# PlacaBaza.net
KiCad netlist of a schematic drawn in Altium Designer
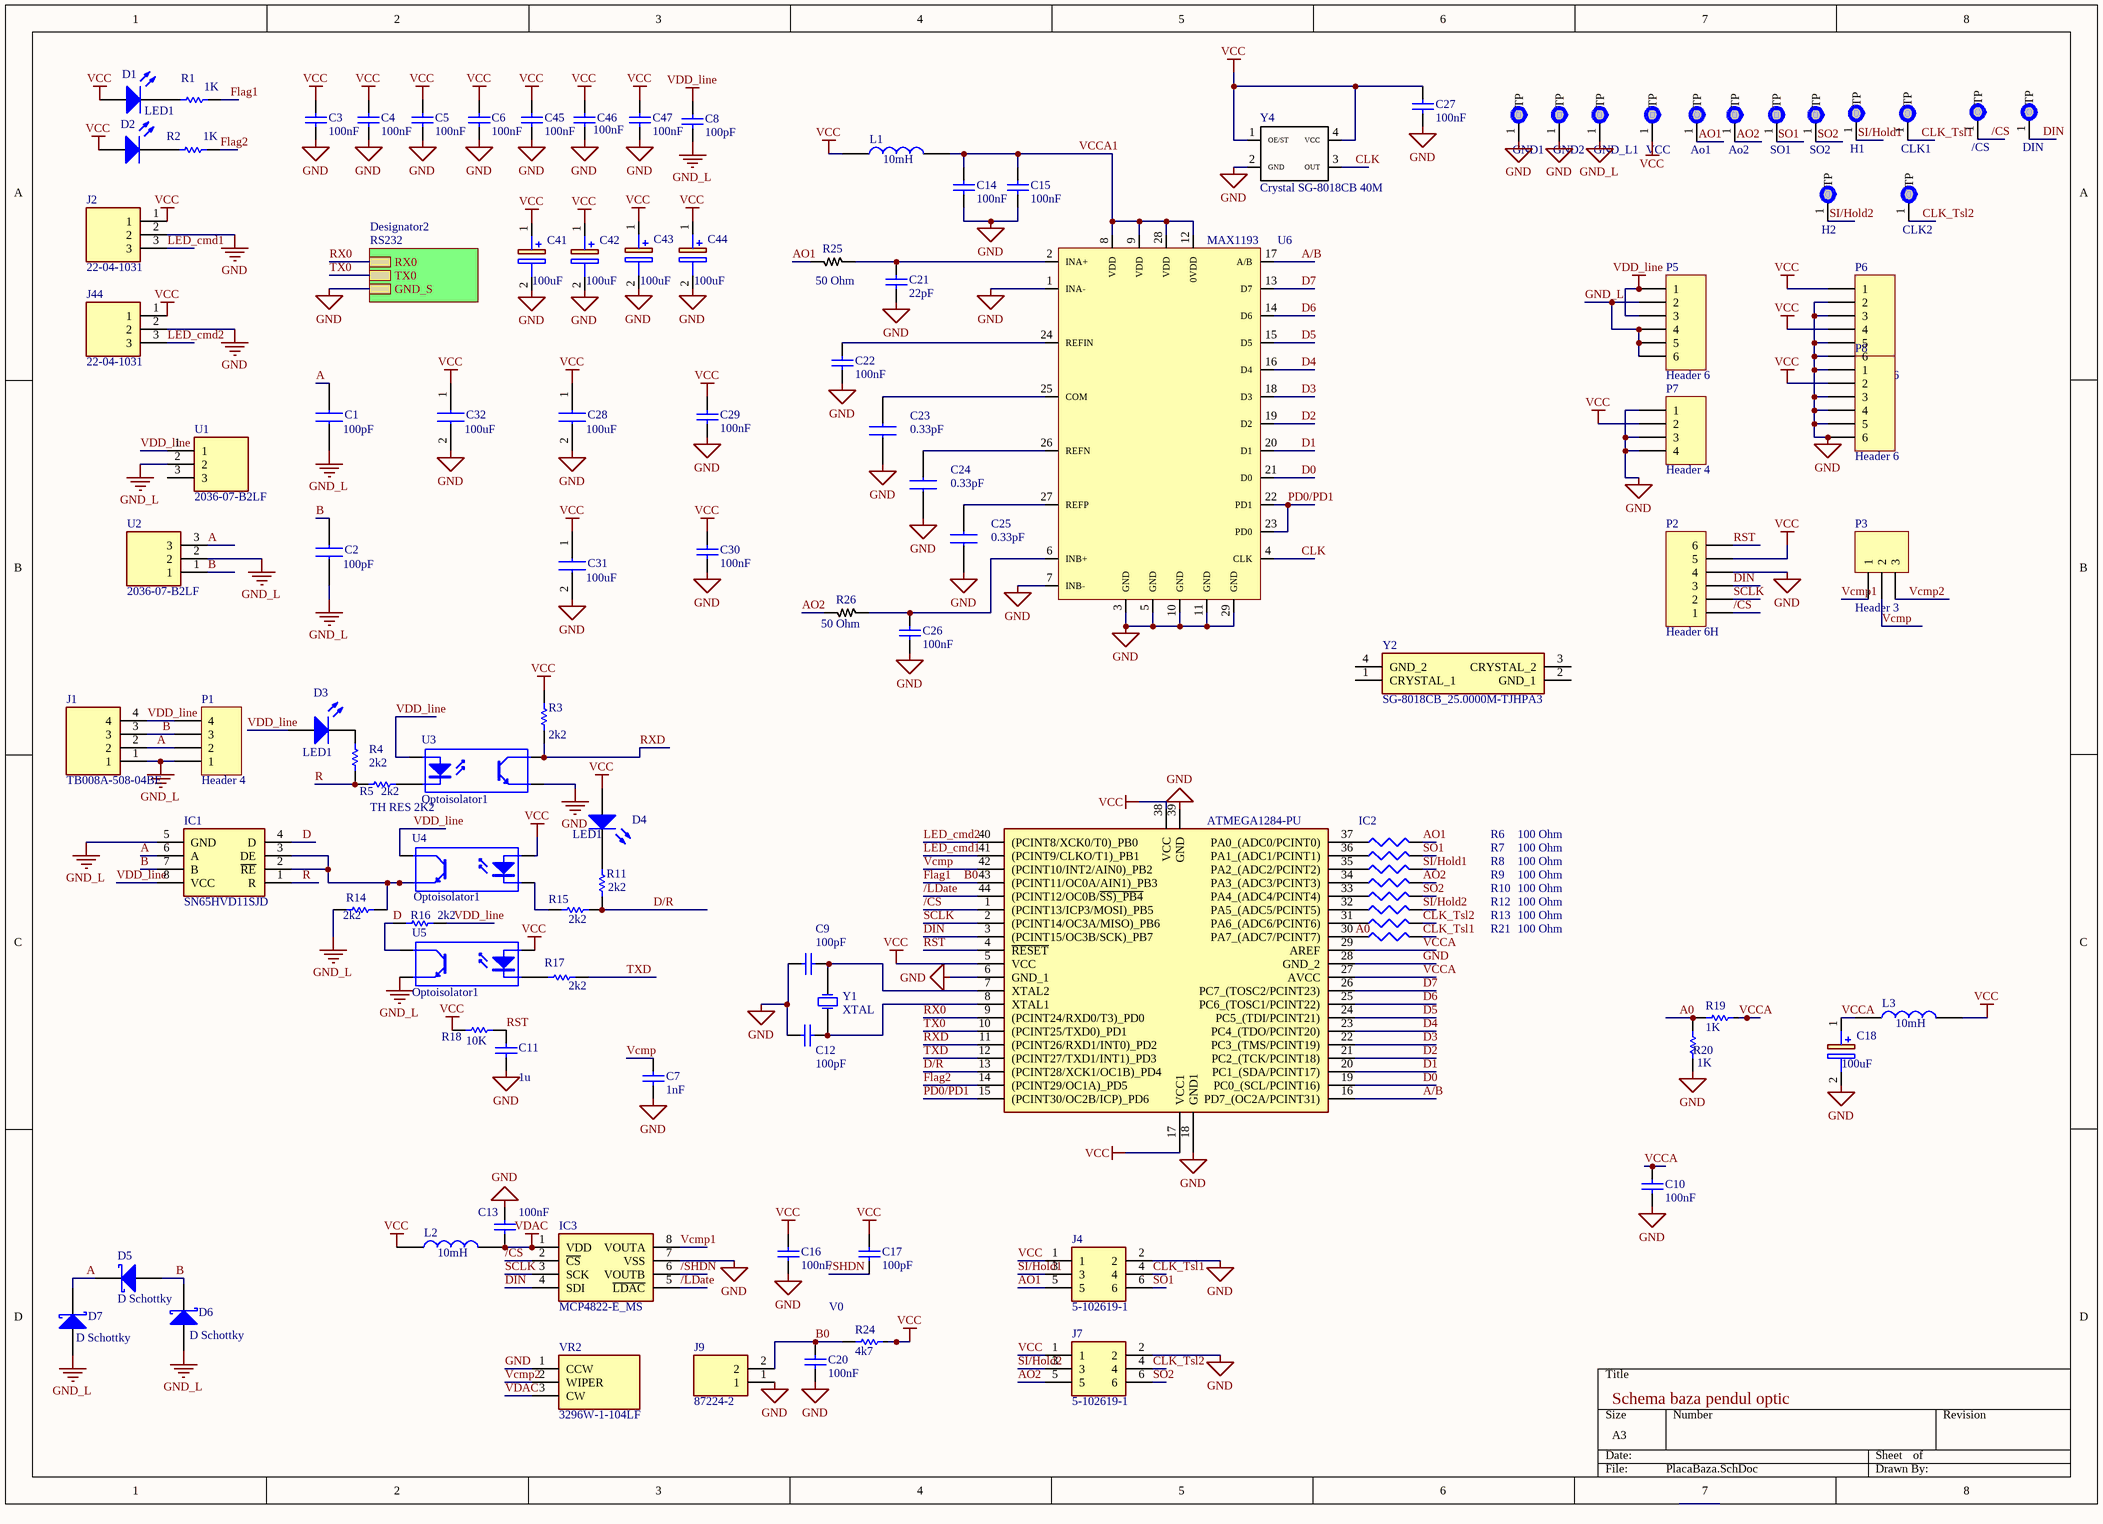
[diagram p0: PlacaBaza.SchDoc]

(export (version "E")
  (design (tool "Eeschema 10.0.6"))
  (components
    (comp (ref "/CS") (value "Testpoint") (footprint "TP") (libsource (lib "my_sch_lib") (part "Test point")))
    (comp (ref "Ao1") (value "Testpoint") (footprint "TP") (libsource (lib "my_sch_lib") (part "Test point")))
    (comp (ref "Ao2") (value "Testpoint") (footprint "TP") (libsource (lib "my_sch_lib") (part "Test point")))
    (comp (ref "C1")
      (value "100pF")
      (footprint "1206 CAP")
      (description "1206CAP 100pF")
      (fields
        (field (name "MANUFACTURER_PART_NUMBER") "04023A101FAT2A")
        (field (name "MOUSER PART NUMBER") "581-04023A101F")
      )
      (libsource (lib "*") (part "04023A101FAT2A"))
    )
    (comp (ref "C2")
      (value "100pF")
      (footprint "1206 CAP")
      (description "1206CAP 100pF")
      (fields
        (field (name "MANUFACTURER_PART_NUMBER") "04023A101FAT2A")
        (field (name "MOUSER PART NUMBER") "581-04023A101F")
      )
      (libsource (lib "*") (part "04023A101FAT2A"))
    )
    (comp (ref "C3")
      (value "100nF")
      (footprint "1206 CAP")
      (description "1206CAP 100nF")
      (fields (field (name "PUBLISHER") "Altium Limited"))
      (libsource (lib "Miscellaneous Devices") (part "Cap"))
    )
    (comp (ref "C4")
      (value "100nF")
      (footprint "1206 CAP")
      (description "1206CAP 100nF")
      (fields (field (name "PUBLISHER") "Altium Limited"))
      (libsource (lib "Miscellaneous Devices") (part "Cap"))
    )
    (comp (ref "C5")
      (value "100nF")
      (footprint "1206 CAP")
      (description "1206CAP 100nF")
      (fields (field (name "PUBLISHER") "Altium Limited"))
      (libsource (lib "Miscellaneous Devices") (part "Cap"))
    )
    (comp (ref "C6")
      (value "100nF")
      (footprint "1206 CAP")
      (description "1206CAP 100nF")
      (fields (field (name "PUBLISHER") "Altium Limited"))
      (libsource (lib "Miscellaneous Devices") (part "Cap"))
    )
    (comp (ref "C7")
      (value "1nF")
      (footprint "1206 CAP")
      (description "1206CAP 1nF")
      (fields (field (name "PUBLISHER") "Altium Limited"))
      (libsource (lib "Miscellaneous Devices") (part "Cap"))
    )
    (comp (ref "C8")
      (value "100pF")
      (footprint "1206 CAP")
      (description "1206CAP 100nF")
      (fields (field (name "PUBLISHER") "Altium Limited"))
      (libsource (lib "Miscellaneous Devices") (part "Cap"))
    )
    (comp (ref "C9")
      (value "100pF")
      (footprint "1206 CAP")
      (description "1206CAP 100pF")
      (fields (field (name "PUBLISHER") "Altium Limited"))
      (libsource (lib "Miscellaneous Devices") (part "Cap Semi"))
    )
    (comp (ref "C10")
      (value "100nF")
      (footprint "1206 CAP")
      (description "1206CAP 100nF")
      (fields (field (name "PUBLISHER") "Altium Limited"))
      (libsource (lib "Miscellaneous Devices") (part "Cap"))
    )
    (comp (ref "C11")
      (value "1u")
      (footprint "1206 CAP")
      (description "1206CAP 1uF")
      (fields (field (name "PUBLISHER") "Altium Limited"))
      (libsource (lib "Miscellaneous Devices") (part "Cap"))
    )
    (comp (ref "C12")
      (value "100pF")
      (footprint "1206 CAP")
      (description "1206CAP 100pF")
      (fields (field (name "PUBLISHER") "Altium Limited"))
      (libsource (lib "Miscellaneous Devices") (part "Cap Semi"))
    )
    (comp (ref "C13")
      (value "100nF")
      (footprint "1206 CAP")
      (description "1206CAP 100nF")
      (fields (field (name "PUBLISHER") "Altium Limited"))
      (libsource (lib "Miscellaneous Devices") (part "Cap"))
    )
    (comp (ref "C14")
      (value "100nF")
      (footprint "1206 CAP")
      (description "1206CAP 100nF")
      (fields (field (name "PUBLISHER") "Altium Limited"))
      (libsource (lib "Miscellaneous Devices") (part "Cap"))
    )
    (comp (ref "C15")
      (value "100nF")
      (footprint "1206 CAP")
      (description "1206CAP 100nF")
      (fields (field (name "PUBLISHER") "Altium Limited"))
      (libsource (lib "Miscellaneous Devices") (part "Cap"))
    )
    (comp (ref "C16")
      (value "100nF")
      (footprint "1206 CAP")
      (description "1206CAP 100nF")
      (fields (field (name "PUBLISHER") "Altium Limited"))
      (libsource (lib "Miscellaneous Devices") (part "Cap"))
    )
    (comp (ref "C17")
      (value "100pF")
      (footprint "1206 CAP")
      (description "1206CAP 100pF")
      (fields (field (name "PUBLISHER") "Altium Limited"))
      (libsource (lib "Miscellaneous Devices") (part "Cap"))
    )
    (comp (ref "C18")
      (value "100uF")
      (footprint "CAPPRD275W50D630H1100")
      (description "polarized cap 2.75 pitch")
      (fields
        (field (name "MANUFACTURER_PART_NUMBER") "MAL215299601E3")
        (field (name "MOUSER PART NUMBER") "594-MAL215299601E3")
      )
      (libsource (lib "*") (part "MAL215299601E3"))
    )
    (comp (ref "C20")
      (value "100nF")
      (footprint "1206 CAP")
      (description "1206CAP 100nF")
      (fields (field (name "PUBLISHER") "Altium Limited"))
      (libsource (lib "Miscellaneous Devices") (part "Cap"))
    )
    (comp (ref "C21")
      (value "22pF")
      (footprint "1206 CAP")
      (description "1206CAP 22pF")
      (fields (field (name "PUBLISHER") "Altium Limited"))
      (libsource (lib "Miscellaneous Devices") (part "Cap"))
    )
    (comp (ref "C22")
      (value "100nF")
      (footprint "1206 CAP")
      (description "1206CAP 100nF")
      (fields (field (name "PUBLISHER") "Altium Limited"))
      (libsource (lib "Miscellaneous Devices") (part "Cap"))
    )
    (comp (ref "C23")
      (value "0.33pF")
      (footprint "0805")
      (description "1206CAP 0.33uF")
      (fields
        (field (name "MANUFACTURER_PART_NUMBER") "08055A150JAT2A")
        (field (name "MOUSER PART NUMBER") "581-08055A150J")
      )
      (libsource (lib "*") (part "08055A150JAT2A"))
    )
    (comp (ref "C24")
      (value "0.33pF")
      (footprint "0805")
      (description "1206CAP 0.33uF")
      (fields
        (field (name "MANUFACTURER_PART_NUMBER") "08055A150JAT2A")
        (field (name "MOUSER PART NUMBER") "581-08055A150J")
      )
      (libsource (lib "*") (part "08055A150JAT2A"))
    )
    (comp (ref "C25")
      (value "0.33pF")
      (footprint "0805")
      (description "1206CAP 0.33uF")
      (fields
        (field (name "MANUFACTURER_PART_NUMBER") "08055A150JAT2A")
        (field (name "MOUSER PART NUMBER") "581-08055A150J")
      )
      (libsource (lib "*") (part "08055A150JAT2A"))
    )
    (comp (ref "C26")
      (value "100nF")
      (footprint "1206 CAP")
      (description "1206CAP 100nF")
      (fields (field (name "PUBLISHER") "Altium Limited"))
      (libsource (lib "Miscellaneous Devices") (part "Cap"))
    )
    (comp (ref "C27")
      (value "100nF")
      (footprint "1206 CAP")
      (description "1206CAP 100nF")
      (fields (field (name "PUBLISHER") "Altium Limited"))
      (libsource (lib "Miscellaneous Devices") (part "Cap"))
    )
    (comp (ref "C28")
      (value "100uF")
      (footprint "SamacSys:CAPPRD275W50D630H1100")
      (description "polarized cap 2.75mm pitch")
      (fields
        (field (name "MANUFACTURER_PART_NUMBER") "MAL203855101E3")
        (field (name "MOUSER PART NUMBER") "594-MAL203855101E3")
      )
      (libsource (lib "SamacSys") (part "MAL203855101E3"))
    )
    (comp (ref "C29")
      (value "100nF")
      (footprint "1206 CAP")
      (description "1206CAP 100nF")
      (fields (field (name "PUBLISHER") "Altium Limited"))
      (libsource (lib "Miscellaneous Devices") (part "Cap"))
    )
    (comp (ref "C30")
      (value "100nF")
      (footprint "1206 CAP")
      (description "1206CAP 100nF")
      (fields (field (name "PUBLISHER") "Altium Limited"))
      (libsource (lib "Miscellaneous Devices") (part "Cap"))
    )
    (comp (ref "C31")
      (value "100uF")
      (footprint "SamacSys:CAPPRD275W50D630H1100")
      (description "polarized cap 2.75mm pitch")
      (fields
        (field (name "MANUFACTURER_PART_NUMBER") "MAL203855101E3")
        (field (name "MOUSER PART NUMBER") "594-MAL203855101E3")
      )
      (libsource (lib "SamacSys") (part "MAL203855101E3"))
    )
    (comp (ref "C32")
      (value "100uF")
      (footprint "SamacSys:CAPPRD275W50D630H1100")
      (description "polarized cap 2.75mm pitch")
      (fields
        (field (name "MANUFACTURER_PART_NUMBER") "MAL203855101E3")
        (field (name "MOUSER PART NUMBER") "594-MAL203855101E3")
      )
      (libsource (lib "SamacSys") (part "MAL203855101E3"))
    )
    (comp (ref "C41")
      (value "100uF")
      (footprint "CAPPRD275W50D630H1100")
      (description "polarized cap 2.75mm pitch")
      (fields
        (field (name "MANUFACTURER_PART_NUMBER") "MAL215299601E3")
        (field (name "MOUSER PART NUMBER") "594-MAL215299601E3")
      )
      (libsource (lib "*") (part "MAL215299601E3"))
    )
    (comp (ref "C42")
      (value "100uF")
      (footprint "CAPPRD275W50D630H1100")
      (description "polarized cap 2.75mm pitch")
      (fields
        (field (name "MANUFACTURER_PART_NUMBER") "MAL215299601E3")
        (field (name "MOUSER PART NUMBER") "594-MAL215299601E3")
      )
      (libsource (lib "*") (part "MAL215299601E3"))
    )
    (comp (ref "C43")
      (value "100uF")
      (footprint "CAPPRD275W50D630H1100")
      (description "polarized cap 2.75mm pitch")
      (fields
        (field (name "MANUFACTURER_PART_NUMBER") "MAL215299601E3")
        (field (name "MOUSER PART NUMBER") "594-MAL215299601E3")
      )
      (libsource (lib "*") (part "MAL215299601E3"))
    )
    (comp (ref "C44")
      (value "100uF")
      (footprint "CAPPRD275W50D630H1100")
      (description "polarized cap 2.75mm pitch")
      (fields
        (field (name "MANUFACTURER_PART_NUMBER") "MAL215299601E3")
        (field (name "MOUSER PART NUMBER") "594-MAL215299601E3")
      )
      (libsource (lib "*") (part "MAL215299601E3"))
    )
    (comp (ref "C45")
      (value "100nF")
      (footprint "1206 CAP")
      (description "1206CAP 100nF")
      (fields (field (name "PUBLISHER") "Altium Limited"))
      (libsource (lib "Miscellaneous Devices") (part "Cap"))
    )
    (comp (ref "C46")
      (value "100nF")
      (footprint "1206 CAP")
      (description "1206CAP 100nF")
      (fields (field (name "PUBLISHER") "Altium Limited"))
      (libsource (lib "Miscellaneous Devices") (part "Cap"))
    )
    (comp (ref "C47")
      (value "100nF")
      (footprint "1206 CAP")
      (description "1206CAP 100nF")
      (fields (field (name "PUBLISHER") "Altium Limited"))
      (libsource (lib "Miscellaneous Devices") (part "Cap"))
    )
    (comp (ref "CLK1")
      (value "Testpoint")
      (footprint "TP")
      (libsource (lib "my_sch_lib") (part "Test point"))
    )
    (comp (ref "CLK2")
      (value "Testpoint")
      (footprint "TP")
      (libsource (lib "my_sch_lib") (part "Test point"))
    )
    (comp (ref "D1")
      (value "LED1")
      (footprint "LED-1")
      (description "Typical RED GaAs LED")
      (fields (field (name "PUBLISHER") "Altium Limited"))
      (libsource (lib "Miscellaneous Devices") (part "LED1"))
    )
    (comp (ref "D2")
      (value "LED1")
      (footprint "LED-1")
      (description "Typical RED GaAs LED")
      (fields (field (name "PUBLISHER") "Altium Limited"))
      (libsource (lib "Miscellaneous Devices") (part "LED1"))
    )
    (comp (ref "D3")
      (value "LED1")
      (footprint "Miscellaneous Devices:C1206")
      (description "Typical RED GaAs LED")
      (fields (field (name "PUBLISHER") "Altium Limited"))
      (libsource (lib "Miscellaneous Devices") (part "LED1"))
    )
    (comp (ref "D4")
      (value "LED1")
      (footprint "Miscellaneous Devices:C1206")
      (description "Typical RED GaAs LED")
      (fields (field (name "PUBLISHER") "Altium Limited"))
      (libsource (lib "Miscellaneous Devices") (part "LED1"))
    )
    (comp (ref "D5")
      (value "D Schottky")
      (footprint "SMB")
      (description "Schottky Diode")
      (fields (field (name "PUBLISHER") "Altium Limited"))
      (libsource (lib "Miscellaneous Devices") (part "D Schottky"))
    )
    (comp (ref "D6")
      (value "D Schottky")
      (footprint "SMB")
      (description "Schottky Diode")
      (fields (field (name "PUBLISHER") "Altium Limited"))
      (libsource (lib "Miscellaneous Devices") (part "D Schottky"))
    )
    (comp (ref "D7")
      (value "D Schottky")
      (footprint "SMB")
      (description "Schottky Diode")
      (fields (field (name "PUBLISHER") "Altium Limited"))
      (libsource (lib "Miscellaneous Devices") (part "D Schottky"))
    )
    (comp (ref "DIN") (value "Testpoint") (footprint "TP") (libsource (lib "my_sch_lib") (part "Test point")))
    (comp (ref "GND1")
      (value "Testpoint")
      (footprint "TP")
      (libsource (lib "my_sch_lib") (part "Test point"))
    )
    (comp (ref "GND2")
      (value "Testpoint")
      (footprint "TP")
      (libsource (lib "my_sch_lib") (part "Test point"))
    )
    (comp (ref "GND_L1")
      (value "Testpoint")
      (footprint "TP")
      (libsource (lib "my_sch_lib") (part "Test point"))
    )
    (comp (ref "H1") (value "Testpoint") (footprint "TP") (libsource (lib "my_sch_lib") (part "Test point")))
    (comp (ref "H2") (value "Testpoint") (footprint "TP") (libsource (lib "my_sch_lib") (part "Test point")))
    (comp (ref "IC1")
      (value "SN65HVD11SJD")
      (footprint "Miscellaneous Devices:DIP-8")
      (description "Integrated Circuit")
      (fields (field (name "MOUSER PART NUMBER") "595-SN65HVD11SJD"))
      (libsource (lib "*") (part "SN65HVD11SJD"))
    )
    (comp (ref "IC2")
      (value "ATMEGA1284-PU")
      (footprint "SamacSys:QFP80P1200X1200X120-44N")
      (description "Integrated Circuit")
      (fields (field (name "MOUSER PART NUMBER") "556-ATMEGA1284-PU"))
      (libsource (lib "my_sch_lib") (part "ATMEGA1284-PU"))
    )
    (comp (ref "IC3")
      (value "MCP4822-E_MS")
      (footprint "SamacSys:SOP65P490X110-8N")
      (description "Integrated Circuit")
      (fields
        (field (name "MANUFACTURER_PART_NUMBER") "MCP4822-E/MS")
        (field (name "MOUSER PART NUMBER") "579-MCP4822-E/MS")
      )
      (libsource (lib "*") (part "MCP4822-E_MS"))
    )
    (comp (ref "J1")
      (value "TB008A-508-04BE")
      (footprint "Miscellaneous Connectors:HDR1X4")
      (description "Connector")
      (fields (field (name "MOUSER PART NUMBER") "490-TB008A-508-04BE"))
      (libsource (lib "*") (part "TB008A-508-04BE"))
    )
    (comp (ref "J2")
      (value "22-04-1031")
      (footprint "SamacSys:SHDR3W64P0X250_1X3_700X580X1170P")
      (description "Connector")
      (fields (field (name "MOUSER PART NUMBER") "538-22-04-1031"))
      (libsource (lib "*") (part "22-04-1031"))
    )
    (comp (ref "J4")
      (value "5-102619-1")
      (footprint "SamacSys:SHDR6W66P254_2X3_1473X1016X1118P")
      (description "Connector")
      (fields (field (name "MOUSER PART NUMBER") "571-5-102619-1"))
      (libsource (lib "*") (part "5-102619-1"))
    )
    (comp (ref "J7")
      (value "5-102619-1")
      (footprint "SamacSys:SHDR6W66P254_2X3_1473X1016X1118P")
      (description "Connector")
      (fields (field (name "MOUSER PART NUMBER") "571-5-102619-1"))
      (libsource (lib "*") (part "5-102619-1"))
    )
    (comp (ref "J9")
      (value "87224-2")
      (footprint "SamacSys:872242")
      (description "Connector")
      (fields (field (name "MOUSER PART NUMBER") "571-872242"))
      (libsource (lib "*") (part "87224-2"))
    )
    (comp (ref "J44")
      (value "22-04-1031")
      (footprint "SamacSys:SHDR3W64P0X250_1X3_700X580X1170P")
      (description "Connector")
      (fields (field (name "MOUSER PART NUMBER") "538-22-04-1031"))
      (libsource (lib "*") (part "22-04-1031"))
    )
    (comp (ref "L1")
      (value "10mH")
      (footprint "SamacSys:RLB0608471KL")
      (description "Inductor")
      (fields
        (field (name "MANUFACTURER_PART_NUMBER") "RLB0608-471KL")
        (field (name "MOUSER PART NUMBER") "652-RLB0608-471KL")
      )
      (libsource (lib "SamacSys") (part "RLB0608-471KL"))
    )
    (comp (ref "L2")
      (value "10mH")
      (footprint "SamacSys:RLB0608471KL")
      (description "Inductor")
      (fields
        (field (name "MANUFACTURER_PART_NUMBER") "RLB0608-471KL")
        (field (name "MOUSER PART NUMBER") "652-RLB0608-471KL")
      )
      (libsource (lib "SamacSys") (part "RLB0608-471KL"))
    )
    (comp (ref "L3")
      (value "10mH")
      (footprint "SamacSys:RLB0608471KL")
      (description "Inductor")
      (fields
        (field (name "MANUFACTURER_PART_NUMBER") "RLB0608-471KL")
        (field (name "MOUSER PART NUMBER") "652-RLB0608-471KL")
      )
      (libsource (lib "SamacSys") (part "RLB0608-471KL"))
    )
    (comp (ref "P1")
      (value "Header 4")
      (footprint "HDR1X4")
      (description "Header, 4-Pin")
      (fields (field (name "PUBLISHER") "Altium Limited"))
      (libsource (lib "") (part "Header 4_1"))
    )
    (comp (ref "P2")
      (value "Header 6H")
      (footprint "Miscellaneous Connectors:HDR1X6")
      (description "Header, 6-Pin, Right Angle")
      (fields (field (name "PUBLISHER") "Altium Limited"))
      (libsource (lib "Miscellaneous Connectors") (part "Header 6H"))
    )
    (comp (ref "P3")
      (value "Header 3")
      (footprint "HDR1X3")
      (description "Header, 3-Pin")
      (fields (field (name "PUBLISHER") "Altium Limited"))
      (libsource (lib "Miscellaneous Connectors") (part "Header 3"))
    )
    (comp (ref "P5")
      (value "Header 6")
      (footprint "HDR1X6")
      (description "Header, 6-Pin")
      (fields (field (name "PUBLISHER") "Altium Limited"))
      (libsource (lib "Miscellaneous Connectors") (part "Header 6"))
    )
    (comp (ref "P6")
      (value "Header 6")
      (footprint "HDR1X6")
      (description "Header, 6-Pin")
      (fields (field (name "PUBLISHER") "Altium Limited"))
      (libsource (lib "Miscellaneous Connectors") (part "Header 6"))
    )
    (comp (ref "P7")
      (value "Header 4")
      (footprint "HDR1X4")
      (description "Header, 4-Pin")
      (fields (field (name "PUBLISHER") "Altium Limited"))
      (libsource (lib "Miscellaneous Connectors") (part "Header 4"))
    )
    (comp (ref "P8")
      (value "Header 6")
      (footprint "HDR1X6")
      (description "Header, 6-Pin")
      (fields (field (name "PUBLISHER") "Altium Limited"))
      (libsource (lib "Miscellaneous Connectors") (part "Header 6"))
    )
    (comp (ref "R1")
      (value "1K")
      (footprint "AXIAL-0.3")
      (description "TH RES 1K")
      (fields (field (name "PUBLISHER") "Altium Limited"))
      (libsource (lib "Miscellaneous Devices") (part "Res1"))
    )
    (comp (ref "R2")
      (value "1K")
      (footprint "AXIAL-0.3")
      (description "TH RES 1K")
      (fields (field (name "PUBLISHER") "Altium Limited"))
      (libsource (lib "Miscellaneous Devices") (part "Res1"))
    )
    (comp (ref "R3")
      (value "2k2")
      (footprint "AXIAL-0.3")
      (description "TH RES 2K2")
      (fields (field (name "PUBLISHER") "Altium Limited"))
      (libsource (lib "Miscellaneous Devices") (part "Res1"))
    )
    (comp (ref "R4")
      (value "2k2")
      (footprint "AXIAL-0.3")
      (description "TH RES 2K2")
      (fields (field (name "PUBLISHER") "Altium Limited"))
      (libsource (lib "Miscellaneous Devices") (part "Res1"))
    )
    (comp (ref "R5")
      (value "TH RES 2K2")
      (footprint "AXIAL-0.3")
      (fields (field (name "ALTIUM_VALUE") "2k2") (field (name "PUBLISHER") "Altium Limited"))
      (libsource (lib "Miscellaneous Devices") (part "Res1"))
    )
    (comp (ref "R6")
      (value "100 Ohm")
      (footprint "0805")
      (description "0805RES 100 OHM")
      (fields (field (name "PUBLISHER") "Altium Limited"))
      (libsource (lib "Miscellaneous Devices") (part "Res3"))
    )
    (comp (ref "R7")
      (value "100 Ohm")
      (footprint "0805")
      (description "0805RES 100 OHM")
      (fields (field (name "PUBLISHER") "Altium Limited"))
      (libsource (lib "Miscellaneous Devices") (part "Res3"))
    )
    (comp (ref "R8")
      (value "100 Ohm")
      (footprint "0805")
      (description "0805RES 100 OHM")
      (fields (field (name "PUBLISHER") "Altium Limited"))
      (libsource (lib "Miscellaneous Devices") (part "Res3"))
    )
    (comp (ref "R9")
      (value "100 Ohm")
      (footprint "0805")
      (description "0805RES 100 OHM")
      (fields (field (name "PUBLISHER") "Altium Limited"))
      (libsource (lib "Miscellaneous Devices") (part "Res3"))
    )
    (comp (ref "R10")
      (value "100 Ohm")
      (footprint "0805")
      (description "0805RES 100 OHM")
      (fields (field (name "PUBLISHER") "Altium Limited"))
      (libsource (lib "Miscellaneous Devices") (part "Res3"))
    )
    (comp (ref "R11")
      (value "2k2")
      (footprint "AXIAL-0.3")
      (description "TH RES 2K2")
      (fields (field (name "PUBLISHER") "Altium Limited"))
      (libsource (lib "Miscellaneous Devices") (part "Res1"))
    )
    (comp (ref "R12")
      (value "100 Ohm")
      (footprint "0805")
      (description "0805RES 100 OHM")
      (fields (field (name "PUBLISHER") "Altium Limited"))
      (libsource (lib "Miscellaneous Devices") (part "Res3"))
    )
    (comp (ref "R13")
      (value "100 Ohm")
      (footprint "0805")
      (description "0805RES 100 OHM")
      (fields (field (name "PUBLISHER") "Altium Limited"))
      (libsource (lib "Miscellaneous Devices") (part "Res3"))
    )
    (comp (ref "R14")
      (value "2k2")
      (footprint "AXIAL-0.3")
      (description "TH RES 2K2")
      (fields (field (name "PUBLISHER") "Altium Limited"))
      (libsource (lib "Miscellaneous Devices") (part "Res1"))
    )
    (comp (ref "R15")
      (value "2k2")
      (footprint "AXIAL-0.3")
      (description "TH RES 2K2")
      (fields (field (name "PUBLISHER") "Altium Limited"))
      (libsource (lib "Miscellaneous Devices") (part "Res1"))
    )
    (comp (ref "R16")
      (value "2k2")
      (footprint "AXIAL-0.3")
      (description "TH RES 2K2")
      (fields (field (name "PUBLISHER") "Altium Limited"))
      (libsource (lib "Miscellaneous Devices") (part "Res1"))
    )
    (comp (ref "R17")
      (value "2k2")
      (footprint "AXIAL-0.3")
      (description "TH RES 2K2")
      (fields (field (name "PUBLISHER") "Altium Limited"))
      (libsource (lib "Miscellaneous Devices") (part "Res1"))
    )
    (comp (ref "R18")
      (value "10K")
      (footprint "Miscellaneous Devices:C1206")
      (description "TH RES 2K2")
      (fields (field (name "PUBLISHER") "Altium Limited"))
      (libsource (lib "Miscellaneous Devices") (part "Res1"))
    )
    (comp (ref "R19")
      (value "1K")
      (footprint "1206 CAP")
      (description "1206RES 1K")
      (fields (field (name "PUBLISHER") "Altium Limited"))
      (libsource (lib "Miscellaneous Devices") (part "Res1"))
    )
    (comp (ref "R20")
      (value "1K")
      (footprint "1206 CAP")
      (description "1206RES 1K")
      (fields (field (name "PUBLISHER") "Altium Limited"))
      (libsource (lib "Miscellaneous Devices") (part "Res1"))
    )
    (comp (ref "R21")
      (value "100 Ohm")
      (footprint "0805")
      (description "0805RES 100 OHM")
      (fields (field (name "PUBLISHER") "Altium Limited"))
      (libsource (lib "Miscellaneous Devices") (part "Res3"))
    )
    (comp (ref "R24")
      (value "4k7")
      (footprint "1206 CAP")
      (description "1206RES 4K7")
      (fields (field (name "PUBLISHER") "Altium Limited"))
      (libsource (lib "Miscellaneous Devices") (part "Res1"))
    )
    (comp (ref "R25")
      (value "50 Ohm")
      (footprint "0805")
      (description "0805RES 50 OHM")
      (libsource (lib "Basic components") (part "RES 0402"))
    )
    (comp (ref "R26")
      (value "50 Ohm")
      (footprint "0805")
      (description "0805RES 50 OHM")
      (libsource (lib "Basic components") (part "RES 0402"))
    )
    (comp (ref "SO1") (value "Testpoint") (footprint "TP") (libsource (lib "my_sch_lib") (part "Test point")))
    (comp (ref "SO2") (value "Testpoint") (footprint "TP") (libsource (lib "my_sch_lib") (part "Test point")))
    (comp (ref "U1")
      (value "2036-07-B2LF")
      (footprint "SamacSys:203607B2LF")
      (description "Undefined or Miscellaneous")
      (fields (field (name "MOUSER PART NUMBER") "652-2036-07-B2LF"))
      (libsource (lib "*") (part "2036-07-B2LF"))
    )
    (comp (ref "U2")
      (value "2036-07-B2LF")
      (footprint "SamacSys:203607B2LF")
      (description "Undefined or Miscellaneous")
      (fields (field (name "MOUSER PART NUMBER") "652-2036-07-B2LF"))
      (libsource (lib "") (part "2036-07-B2LF_1"))
    )
    (comp (ref "U3")
      (value "Optoisolator1")
      (footprint "DIP-4")
      (description "4-Pin Phototransistor Optocoupler")
      (fields (field (name "PUBLISHER") "Altium Limited"))
      (libsource (lib "Miscellaneous Devices") (part "Optoisolator1"))
    )
    (comp (ref "U4")
      (value "Optoisolator1")
      (footprint "DIP-4")
      (description "4-Pin Phototransistor Optocoupler")
      (fields (field (name "PUBLISHER") "Altium Limited"))
      (libsource (lib "Miscellaneous Devices") (part "Optoisolator1"))
    )
    (comp (ref "U5")
      (value "Optoisolator1")
      (footprint "DIP-4")
      (description "4-Pin Phototransistor Optocoupler")
      (fields (field (name "PUBLISHER") "Altium Limited"))
      (libsource (lib "Miscellaneous Devices") (part "Optoisolator1"))
    )
    (comp (ref "U6")
      (value "MAX1193")
      (footprint "QFN50P500X500X80_HS-29N")
      (libsource (lib "my_sch_lib") (part "MAX1193"))
    )
    (comp (ref "VCC") (value "Testpoint") (footprint "TP") (libsource (lib "my_sch_lib") (part "Test point")))
    (comp (ref "VR2")
      (value "3296W-1-104LF")
      (footprint "SamacSys:3296W-1")
      (description "Variable Resistor")
      (fields (field (name "MOUSER PART NUMBER") "652-3296W-1-104LF"))
      (libsource (lib "*") (part "3296W-1-104LF"))
    )
    (comp (ref "Y1")
      (value "XTAL")
      (footprint "Miscellaneous Devices:RAD-0.2")
      (description "Crystal Oscillator")
      (fields (field (name "PUBLISHER") "Altium Limited"))
      (libsource (lib "Miscellaneous Devices") (part "XTAL"))
    )
    (comp (ref "Y2")
      (value "SG-8018CB_25.0000M-TJHPA3")
      (footprint "SamacSys:SG8018CB250000MTJHPA3")
      (description "Crystal or Oscillator")
      (fields
        (field (name "MANUFACTURER_PART_NUMBER") "SG-8018CB 25.0000M-TJHPA3")
        (field (name "MOUSER PART NUMBER") "732-CB25M-TJHPA3")
      )
      (libsource (lib "SamacSys") (part "SG-8018CB_25.0000M-TJHPA3"))
    )
    (comp (ref "Y4")
      (value "Crystal SG-8018CB 40M")
      (footprint "SG-8018CB")
      (libsource (lib "my_sch_lib") (part "Crystal SG-8018CB 40M"))
    )
  )
  (nets
    (net (code "1") (name "/A") (class "Default")
      (node (ref "C1") (pin "2") (pinfunction "2_2") (pintype "passive"))
      (node (ref "D5") (pin "2") (pinfunction "K_2") (pintype "passive"))
      (node (ref "D7") (pin "2") (pinfunction "K_2") (pintype "passive"))
      (node (ref "IC1") (pin "6") (pinfunction "A_6") (pintype "passive"))
      (node (ref "J1") (pin "2") (pinfunction "2_2") (pintype "passive"))
      (node (ref "P1") (pin "2") (pinfunction "2_2") (pintype "passive"))
      (node (ref "U2") (pin "3") (pinfunction "3_3") (pintype "passive"))
    )
    (net (code "2") (name "/A0") (class "Default")
      (node (ref "IC2") (pin "30") (pinfunction "PA7_(ADC7/PCINT7)_30") (pintype "passive"))
      (node (ref "R19") (pin "1") (pinfunction "1_1") (pintype "passive"))
      (node (ref "R20") (pin "2") (pinfunction "2_2") (pintype "passive"))
      (node (ref "R21") (pin "1") (pinfunction "1_1") (pintype "passive"))
    )
    (net (code "3") (name "/AO1") (class "Default")
      (node (ref "Ao1") (pin "1") (pinfunction "TP_1") (pintype "passive"))
      (node (ref "J4") (pin "5") (pinfunction "5_5") (pintype "passive"))
      (node (ref "R25") (pin "2") (pinfunction "2_2") (pintype "passive"))
      (node (ref "R6") (pin "2") (pinfunction "2_2") (pintype "passive"))
    )
    (net (code "4") (name "/AO2") (class "Default")
      (node (ref "Ao2") (pin "1") (pinfunction "TP_1") (pintype "passive"))
      (node (ref "J7") (pin "5") (pinfunction "5_5") (pintype "passive"))
      (node (ref "R26") (pin "2") (pinfunction "2_2") (pintype "passive"))
      (node (ref "R9") (pin "2") (pinfunction "2_2") (pintype "passive"))
    )
    (net (code "5") (name "/A{slash}B") (class "Default")
      (node (ref "IC2") (pin "16") (pinfunction "PD7_(OC2A/PCINT31)_16") (pintype "passive"))
      (node (ref "U6") (pin "17") (pinfunction "A/B_17") (pintype "passive"))
    )
    (net (code "6") (name "/B") (class "Default")
      (node (ref "C2") (pin "2") (pinfunction "2_2") (pintype "passive"))
      (node (ref "D5") (pin "1") (pinfunction "A_1") (pintype "passive"))
      (node (ref "D6") (pin "2") (pinfunction "K_2") (pintype "passive"))
      (node (ref "IC1") (pin "7") (pinfunction "B_7") (pintype "passive"))
      (node (ref "J1") (pin "3") (pinfunction "3_3") (pintype "passive"))
      (node (ref "P1") (pin "3") (pinfunction "3_3") (pintype "passive"))
      (node (ref "U2") (pin "1") (pinfunction "1_1") (pintype "passive"))
    )
    (net (code "7") (name "/B0") (class "Default")
      (node (ref "C20") (pin "2") (pinfunction "2_2") (pintype "passive"))
      (node (ref "IC2") (pin "43") (pinfunction "(PCINT11/OC0A/AIN1)_PB3_43") (pintype "passive"))
      (node (ref "J9") (pin "2") (pinfunction "2_2") (pintype "passive"))
      (node (ref "R1") (pin "1") (pinfunction "1_1") (pintype "passive"))
      (node (ref "R24") (pin "1") (pinfunction "1_1") (pintype "passive"))
    )
    (net (code "8") (name "/CLK") (class "Default")
      (node (ref "U6") (pin "4") (pinfunction "CLK_4") (pintype "passive"))
      (node (ref "Y4") (pin "3") (pinfunction "OUT_3") (pintype "passive"))
    )
    (net (code "9") (name "/CLK_Tsl1") (class "Default")
      (node (ref "CLK1") (pin "1") (pinfunction "TP_1") (pintype "passive"))
      (node (ref "J4") (pin "4") (pinfunction "4_4") (pintype "passive"))
      (node (ref "R21") (pin "2") (pinfunction "2_2") (pintype "passive"))
    )
    (net (code "10") (name "/CLK_Tsl2") (class "Default")
      (node (ref "CLK2") (pin "1") (pinfunction "TP_1") (pintype "passive"))
      (node (ref "J7") (pin "4") (pinfunction "4_4") (pintype "passive"))
      (node (ref "R13") (pin "2") (pinfunction "2_2") (pintype "passive"))
    )
    (net (code "11") (name "/D") (class "Default")
      (node (ref "IC1") (pin "4") (pinfunction "D_4") (pintype "passive"))
      (node (ref "R16") (pin "1") (pinfunction "1_1") (pintype "passive"))
      (node (ref "U5") (pin "4") (pinfunction "C_4") (pintype "passive"))
    )
    (net (code "12") (name "/D0") (class "Default")
      (node (ref "IC2") (pin "19") (pinfunction "PC0_(SCL/PCINT16)_19") (pintype "passive"))
      (node (ref "U6") (pin "21") (pinfunction "D0_21") (pintype "passive"))
    )
    (net (code "13") (name "/D1") (class "Default")
      (node (ref "IC2") (pin "20") (pinfunction "PC1_(SDA/PCINT17)_20") (pintype "passive"))
      (node (ref "U6") (pin "20") (pinfunction "D1_20") (pintype "passive"))
    )
    (net (code "14") (name "/D2") (class "Default")
      (node (ref "IC2") (pin "21") (pinfunction "PC2_(TCK/PCINT18)_21") (pintype "passive"))
      (node (ref "U6") (pin "19") (pinfunction "D2_19") (pintype "passive"))
    )
    (net (code "15") (name "/D3") (class "Default")
      (node (ref "IC2") (pin "22") (pinfunction "PC3_(TMS/PCINT19)_22") (pintype "passive"))
      (node (ref "U6") (pin "18") (pinfunction "D3_18") (pintype "passive"))
    )
    (net (code "16") (name "/D4") (class "Default")
      (node (ref "IC2") (pin "23") (pinfunction "PC4_(TDO/PCINT20)_23") (pintype "passive"))
      (node (ref "U6") (pin "16") (pinfunction "D4_16") (pintype "passive"))
    )
    (net (code "17") (name "/D5") (class "Default")
      (node (ref "IC2") (pin "24") (pinfunction "PC5_(TDI/PCINT21)_24") (pintype "passive"))
      (node (ref "U6") (pin "15") (pinfunction "D5_15") (pintype "passive"))
    )
    (net (code "18") (name "/D6") (class "Default")
      (node (ref "IC2") (pin "25") (pinfunction "PC6_(TOSC1/PCINT22)_25") (pintype "passive"))
      (node (ref "U6") (pin "14") (pinfunction "D6_14") (pintype "passive"))
    )
    (net (code "19") (name "/D7") (class "Default")
      (node (ref "IC2") (pin "26") (pinfunction "PC7_(TOSC2/PCINT23)_26") (pintype "passive"))
      (node (ref "U6") (pin "13") (pinfunction "D7_13") (pintype "passive"))
    )
    (net (code "20") (name "/DIN") (class "Default")
      (node (ref "DIN") (pin "1") (pinfunction "TP_1") (pintype "passive"))
      (node (ref "IC2") (pin "3") (pinfunction "(PCINT15/OC3B/SCK)_PB7_3") (pintype "passive"))
      (node (ref "IC3") (pin "4") (pinfunction "SDI_4") (pintype "passive"))
      (node (ref "P2") (pin "3") (pinfunction "3_3") (pintype "passive"))
    )
    (net (code "21") (name "/D{slash}R") (class "Default")
      (node (ref "IC2") (pin "13") (pinfunction "(PCINT28/XCK1/OC1B)_PD4_13") (pintype "passive"))
      (node (ref "R11") (pin "1") (pinfunction "1_1") (pintype "passive"))
      (node (ref "R15") (pin "2") (pinfunction "2_2") (pintype "passive"))
    )
    (net (code "22") (name "/Flag2") (class "Default")
      (node (ref "IC2") (pin "14") (pinfunction "(PCINT29/OC1A)_PD5_14") (pintype "passive"))
      (node (ref "R2") (pin "1") (pinfunction "1_1") (pintype "passive"))
    )
    (net (code "23") (name "/LED_cmd1") (class "Default")
      (node (ref "IC2") (pin "41") (pinfunction "(PCINT9/CLKO/T1)_PB1_41") (pintype "passive"))
      (node (ref "J2") (pin "3") (pinfunction "3_3") (pintype "passive"))
    )
    (net (code "24") (name "/LED_cmd2") (class "Default")
      (node (ref "IC2") (pin "40") (pinfunction "(PCINT8/XCK0/T0)_PB0_40") (pintype "passive"))
      (node (ref "J44") (pin "3") (pinfunction "3_3") (pintype "passive"))
    )
    (net (code "25") (name "/PD0{slash}PD1") (class "Default")
      (node (ref "IC2") (pin "15") (pinfunction "(PCINT30/OC2B/ICP)_PD6_15") (pintype "passive"))
      (node (ref "U6") (pin "22") (pinfunction "PD1_22") (pintype "passive"))
      (node (ref "U6") (pin "23") (pinfunction "PD0_23") (pintype "passive"))
    )
    (net (code "26") (name "/R") (class "Default")
      (node (ref "IC1") (pin "1") (pinfunction "R_1") (pintype "passive"))
      (node (ref "R4") (pin "1") (pinfunction "1_1") (pintype "passive"))
      (node (ref "R5") (pin "1") (pinfunction "1_1") (pintype "passive"))
    )
    (net (code "27") (name "/RST") (class "Default")
      (node (ref "C11") (pin "2") (pinfunction "2_2") (pintype "passive"))
      (node (ref "IC2") (pin "4") (pinfunction "~{RESET}_4") (pintype "passive"))
      (node (ref "P2") (pin "6") (pinfunction "6_6") (pintype "passive"))
      (node (ref "R18") (pin "2") (pinfunction "2_2") (pintype "passive"))
    )
    (net (code "28") (name "/RX0") (class "Default")
      (node (ref "IC2") (pin "9") (pinfunction "(PCINT24/RXD0/T3)_PD0_9") (pintype "passive"))
    )
    (net (code "29") (name "/RXD") (class "Default")
      (node (ref "IC2") (pin "11") (pinfunction "(PCINT26/RXD1/INT0)_PD2_11") (pintype "passive"))
      (node (ref "R3") (pin "1") (pinfunction "1_1") (pintype "passive"))
      (node (ref "U3") (pin "4") (pinfunction "C_4") (pintype "passive"))
    )
    (net (code "30") (name "/SCLK") (class "Default")
      (node (ref "IC2") (pin "2") (pinfunction "(PCINT14/OC3A/MISO)_PB6_2") (pintype "passive"))
      (node (ref "IC3") (pin "3") (pinfunction "SCK_3") (pintype "passive"))
      (node (ref "P2") (pin "2") (pinfunction "2_2") (pintype "passive"))
    )
    (net (code "31") (name "/SI{slash}Hold1") (class "Default")
      (node (ref "H1") (pin "1") (pinfunction "TP_1") (pintype "passive"))
      (node (ref "J4") (pin "3") (pinfunction "3_3") (pintype "passive"))
      (node (ref "R8") (pin "2") (pinfunction "2_2") (pintype "passive"))
    )
    (net (code "32") (name "/SI{slash}Hold2") (class "Default")
      (node (ref "H2") (pin "1") (pinfunction "TP_1") (pintype "passive"))
      (node (ref "J7") (pin "3") (pinfunction "3_3") (pintype "passive"))
      (node (ref "R12") (pin "2") (pinfunction "2_2") (pintype "passive"))
    )
    (net (code "33") (name "/SO1") (class "Default")
      (node (ref "J4") (pin "6") (pinfunction "6_6") (pintype "passive"))
      (node (ref "R7") (pin "2") (pinfunction "2_2") (pintype "passive"))
      (node (ref "SO1") (pin "1") (pinfunction "TP_1") (pintype "passive"))
    )
    (net (code "34") (name "/SO2") (class "Default")
      (node (ref "J7") (pin "6") (pinfunction "6_6") (pintype "passive"))
      (node (ref "R10") (pin "2") (pinfunction "2_2") (pintype "passive"))
      (node (ref "SO2") (pin "1") (pinfunction "TP_1") (pintype "passive"))
    )
    (net (code "35") (name "/TX0") (class "Default")
      (node (ref "IC2") (pin "10") (pinfunction "(PCINT25/TXD0)_PD1_10") (pintype "passive"))
    )
    (net (code "36") (name "/TXD") (class "Default")
      (node (ref "IC2") (pin "12") (pinfunction "(PCINT27/TXD1/INT1)_PD3_12") (pintype "passive"))
      (node (ref "R17") (pin "2") (pinfunction "2_2") (pintype "passive"))
    )
    (net (code "37") (name "/VCCA") (class "Default")
      (node (ref "C10") (pin "2") (pinfunction "2_2") (pintype "passive"))
      (node (ref "C18") (pin "1") (pinfunction "+_1") (pintype "passive"))
      (node (ref "IC2") (pin "27") (pinfunction "AVCC_27") (pintype "passive"))
      (node (ref "IC2") (pin "29") (pinfunction "AREF_29") (pintype "passive"))
      (node (ref "L3") (pin "1") (pinfunction "1_1") (pintype "passive"))
      (node (ref "R19") (pin "2") (pinfunction "2_2") (pintype "passive"))
    )
    (net (code "38") (name "/VCCA1") (class "Default")
      (node (ref "C14") (pin "2") (pinfunction "2_2") (pintype "passive"))
      (node (ref "C15") (pin "2") (pinfunction "2_2") (pintype "passive"))
      (node (ref "L1") (pin "2") (pinfunction "2_2") (pintype "passive"))
      (node (ref "U6") (pin "12") (pinfunction "0VDD_12") (pintype "passive"))
      (node (ref "U6") (pin "28") (pinfunction "VDD_28") (pintype "passive"))
      (node (ref "U6") (pin "8") (pinfunction "VDD_8") (pintype "passive"))
      (node (ref "U6") (pin "9") (pinfunction "VDD_9") (pintype "passive"))
    )
    (net (code "39") (name "/Vcmp") (class "Default")
      (node (ref "C7") (pin "2") (pinfunction "2_2") (pintype "passive"))
      (node (ref "IC2") (pin "42") (pinfunction "(PCINT10/INT2/AIN0)_PB2_42") (pintype "passive"))
      (node (ref "P3") (pin "2") (pinfunction "2_2") (pintype "passive"))
    )
    (net (code "40") (name "/Vcmp1") (class "Default")
      (node (ref "IC3") (pin "8") (pinfunction "VOUTA_8") (pintype "passive"))
      (node (ref "P3") (pin "1") (pinfunction "1_1") (pintype "passive"))
    )
    (net (code "41") (name "/Vcmp2") (class "Default")
      (node (ref "P3") (pin "3") (pinfunction "3_3") (pintype "passive"))
      (node (ref "VR2") (pin "2") (pinfunction "WIPER_2") (pintype "passive"))
    )
    (net (code "42") (name "/{slash}CS") (class "Default")
      (node (ref "/CS") (pin "1") (pinfunction "TP_1") (pintype "passive"))
      (node (ref "IC2") (pin "1") (pinfunction "(PCINT13/ICP3/MOSI)_PB5_1") (pintype "passive"))
      (node (ref "IC3") (pin "2") (pinfunction "~{CS}_2") (pintype "passive"))
      (node (ref "P2") (pin "1") (pinfunction "1_1") (pintype "passive"))
    )
    (net (code "43") (name "/{slash}LDate") (class "Default")
      (node (ref "IC2") (pin "44") (pinfunction "(PCINT12/OC0B/~{SS)_PB4}_44") (pintype "passive"))
      (node (ref "IC3") (pin "5") (pinfunction "~{LDAC}_5") (pintype "passive"))
    )
    (net (code "44") (name "/{slash}SHDN") (class "Default")
      (node (ref "C17") (pin "1") (pinfunction "1_1") (pintype "passive"))
      (node (ref "IC3") (pin "6") (pinfunction "VOUTB_6") (pintype "passive"))
    )
    (net (code "45") (name "GND") (class "Default")
      (node (ref "C10") (pin "1") (pinfunction "1_1") (pintype "passive"))
      (node (ref "C11") (pin "1") (pinfunction "1_1") (pintype "passive"))
      (node (ref "C12") (pin "1") (pinfunction "1_1") (pintype "passive"))
      (node (ref "C13") (pin "1") (pinfunction "1_1") (pintype "passive"))
      (node (ref "C14") (pin "1") (pinfunction "1_1") (pintype "passive"))
      (node (ref "C15") (pin "1") (pinfunction "1_1") (pintype "passive"))
      (node (ref "C16") (pin "1") (pinfunction "1_1") (pintype "passive"))
      (node (ref "C18") (pin "2") (pinfunction "-_2") (pintype "passive"))
      (node (ref "C20") (pin "1") (pinfunction "1_1") (pintype "passive"))
      (node (ref "C21") (pin "1") (pinfunction "1_1") (pintype "passive"))
      (node (ref "C22") (pin "1") (pinfunction "1_1") (pintype "passive"))
      (node (ref "C23") (pin "1") (pinfunction "1_1") (pintype "passive"))
      (node (ref "C24") (pin "1") (pinfunction "1_1") (pintype "passive"))
      (node (ref "C25") (pin "1") (pinfunction "1_1") (pintype "passive"))
      (node (ref "C26") (pin "1") (pinfunction "1_1") (pintype "passive"))
      (node (ref "C27") (pin "1") (pinfunction "1_1") (pintype "passive"))
      (node (ref "C28") (pin "2") (pinfunction "-_2") (pintype "passive"))
      (node (ref "C29") (pin "1") (pinfunction "1_1") (pintype "passive"))
      (node (ref "C3") (pin "1") (pinfunction "1_1") (pintype "passive"))
      (node (ref "C30") (pin "1") (pinfunction "1_1") (pintype "passive"))
      (node (ref "C31") (pin "2") (pinfunction "-_2") (pintype "passive"))
      (node (ref "C32") (pin "2") (pinfunction "-_2") (pintype "passive"))
      (node (ref "C4") (pin "1") (pinfunction "1_1") (pintype "passive"))
      (node (ref "C41") (pin "2") (pinfunction "-_2") (pintype "passive"))
      (node (ref "C42") (pin "2") (pinfunction "-_2") (pintype "passive"))
      (node (ref "C43") (pin "2") (pinfunction "-_2") (pintype "passive"))
      (node (ref "C44") (pin "2") (pinfunction "-_2") (pintype "passive"))
      (node (ref "C45") (pin "1") (pinfunction "1_1") (pintype "passive"))
      (node (ref "C46") (pin "1") (pinfunction "1_1") (pintype "passive"))
      (node (ref "C47") (pin "1") (pinfunction "1_1") (pintype "passive"))
      (node (ref "C5") (pin "1") (pinfunction "1_1") (pintype "passive"))
      (node (ref "C6") (pin "1") (pinfunction "1_1") (pintype "passive"))
      (node (ref "C7") (pin "1") (pinfunction "1_1") (pintype "passive"))
      (node (ref "C9") (pin "1") (pinfunction "1_1") (pintype "passive"))
      (node (ref "GND1") (pin "1") (pinfunction "TP_1") (pintype "passive"))
      (node (ref "GND2") (pin "1") (pinfunction "TP_1") (pintype "passive"))
      (node (ref "IC2") (pin "18") (pinfunction "GND1_18") (pintype "passive"))
      (node (ref "IC2") (pin "28") (pinfunction "GND_2_28") (pintype "passive"))
      (node (ref "IC2") (pin "39") (pinfunction "GND_39") (pintype "passive"))
      (node (ref "IC2") (pin "6") (pinfunction "GND_1_6") (pintype "passive"))
      (node (ref "IC3") (pin "7") (pinfunction "VSS_7") (pintype "passive"))
      (node (ref "J2") (pin "2") (pinfunction "2_2") (pintype "passive"))
      (node (ref "J4") (pin "2") (pinfunction "2_2") (pintype "passive"))
      (node (ref "J44") (pin "2") (pinfunction "2_2") (pintype "passive"))
      (node (ref "J7") (pin "2") (pinfunction "2_2") (pintype "passive"))
      (node (ref "J9") (pin "1") (pinfunction "1_1") (pintype "passive"))
      (node (ref "P2") (pin "4") (pinfunction "4_4") (pintype "passive"))
      (node (ref "P6") (pin "2") (pinfunction "2_2") (pintype "passive"))
      (node (ref "P6") (pin "3") (pinfunction "3_3") (pintype "passive"))
      (node (ref "P6") (pin "5") (pinfunction "5_5") (pintype "passive"))
      (node (ref "P6") (pin "6") (pinfunction "6_6") (pintype "passive"))
      (node (ref "P7") (pin "1") (pinfunction "1_1") (pintype "passive"))
      (node (ref "P7") (pin "3") (pinfunction "3_3") (pintype "passive"))
      (node (ref "P7") (pin "4") (pinfunction "4_4") (pintype "passive"))
      (node (ref "P8") (pin "1") (pinfunction "1_1") (pintype "passive"))
      (node (ref "P8") (pin "3") (pinfunction "3_3") (pintype "passive"))
      (node (ref "P8") (pin "4") (pinfunction "4_4") (pintype "passive"))
      (node (ref "P8") (pin "5") (pinfunction "5_5") (pintype "passive"))
      (node (ref "P8") (pin "6") (pinfunction "6_6") (pintype "passive"))
      (node (ref "R20") (pin "1") (pinfunction "1_1") (pintype "passive"))
      (node (ref "U3") (pin "3") (pinfunction "E_3") (pintype "passive"))
      (node (ref "U6") (pin "1") (pinfunction "INA-_1") (pintype "passive"))
      (node (ref "U6") (pin "10") (pinfunction "GND_10") (pintype "passive"))
      (node (ref "U6") (pin "11") (pinfunction "GND_11") (pintype "passive"))
      (node (ref "U6") (pin "29") (pinfunction "GND_29") (pintype "passive"))
      (node (ref "U6") (pin "3") (pinfunction "GND_3") (pintype "passive"))
      (node (ref "U6") (pin "5") (pinfunction "GND_5") (pintype "passive"))
      (node (ref "U6") (pin "7") (pinfunction "INB-_7") (pintype "passive"))
      (node (ref "VR2") (pin "1") (pinfunction "CCW_1") (pintype "passive"))
      (node (ref "Y4") (pin "2") (pinfunction "GND_2") (pintype "passive"))
    )
    (net (code "46") (name "GND_L") (class "Default")
      (node (ref "C1") (pin "1") (pinfunction "1_1") (pintype "passive"))
      (node (ref "C2") (pin "1") (pinfunction "1_1") (pintype "passive"))
      (node (ref "C8") (pin "1") (pinfunction "1_1") (pintype "passive"))
      (node (ref "D6") (pin "1") (pinfunction "A_1") (pintype "passive"))
      (node (ref "D7") (pin "1") (pinfunction "A_1") (pintype "passive"))
      (node (ref "GND_L1") (pin "1") (pinfunction "TP_1") (pintype "passive"))
      (node (ref "IC1") (pin "5") (pinfunction "GND_5") (pintype "passive"))
      (node (ref "J1") (pin "1") (pinfunction "1_1") (pintype "passive"))
      (node (ref "P1") (pin "1") (pinfunction "1_1") (pintype "passive"))
      (node (ref "P5") (pin "2") (pinfunction "2_2") (pintype "passive"))
      (node (ref "P5") (pin "4") (pinfunction "4_4") (pintype "passive"))
      (node (ref "P5") (pin "5") (pinfunction "5_5") (pintype "passive"))
      (node (ref "P5") (pin "6") (pinfunction "6_6") (pintype "passive"))
      (node (ref "R14") (pin "1") (pinfunction "1_1") (pintype "passive"))
      (node (ref "U1") (pin "2") (pinfunction "2_2") (pintype "passive"))
      (node (ref "U2") (pin "2") (pinfunction "2_2") (pintype "passive"))
      (node (ref "U5") (pin "3") (pinfunction "E_3") (pintype "passive"))
    )
    (net (code "47") (name "Net-(D1-K)") (class "Default")
      (node (ref "D1") (pin "2") (pinfunction "K_2") (pintype "passive"))
      (node (ref "R1") (pin "2") (pinfunction "2_2") (pintype "passive"))
    )
    (net (code "48") (name "Net-(D2-K)") (class "Default")
      (node (ref "D2") (pin "2") (pinfunction "K_2") (pintype "passive"))
      (node (ref "R2") (pin "2") (pinfunction "2_2") (pintype "passive"))
    )
    (net (code "49") (name "Net-(D3-K)") (class "Default")
      (node (ref "D3") (pin "2") (pinfunction "K_2") (pintype "passive"))
      (node (ref "R4") (pin "2") (pinfunction "2_2") (pintype "passive"))
    )
    (net (code "50") (name "Net-(D4-K)") (class "Default")
      (node (ref "D4") (pin "2") (pinfunction "K_2") (pintype "passive"))
      (node (ref "R11") (pin "2") (pinfunction "2_2") (pintype "passive"))
    )
    (net (code "51") (name "Net-(IC1-DE)") (class "Default")
      (node (ref "IC1") (pin "2") (pinfunction "~{RE}_2") (pintype "passive"))
      (node (ref "IC1") (pin "3") (pinfunction "DE_3") (pintype "passive"))
      (node (ref "R14") (pin "2") (pinfunction "2_2") (pintype "passive"))
      (node (ref "U4") (pin "3") (pinfunction "E_3") (pintype "passive"))
    )
    (net (code "52") (name "Net-(IC2-PA0_(ADC0{slash}PCINT0))") (class "Default")
      (node (ref "IC2") (pin "37") (pinfunction "PA0_(ADC0/PCINT0)_37") (pintype "passive"))
      (node (ref "R6") (pin "1") (pinfunction "1_1") (pintype "passive"))
    )
    (net (code "53") (name "Net-(IC2-PA1_(ADC1{slash}PCINT1))") (class "Default")
      (node (ref "IC2") (pin "36") (pinfunction "PA1_(ADC1/PCINT1)_36") (pintype "passive"))
      (node (ref "R7") (pin "1") (pinfunction "1_1") (pintype "passive"))
    )
    (net (code "54") (name "Net-(IC2-PA2_(ADC2{slash}PCINT2))") (class "Default")
      (node (ref "IC2") (pin "35") (pinfunction "PA2_(ADC2/PCINT2)_35") (pintype "passive"))
      (node (ref "R8") (pin "1") (pinfunction "1_1") (pintype "passive"))
    )
    (net (code "55") (name "Net-(IC2-PA3_(ADC3{slash}PCINT3))") (class "Default")
      (node (ref "IC2") (pin "34") (pinfunction "PA3_(ADC3/PCINT3)_34") (pintype "passive"))
      (node (ref "R9") (pin "1") (pinfunction "1_1") (pintype "passive"))
    )
    (net (code "56") (name "Net-(IC2-PA4_(ADC4{slash}PCINT4))") (class "Default")
      (node (ref "IC2") (pin "33") (pinfunction "PA4_(ADC4/PCINT4)_33") (pintype "passive"))
      (node (ref "R10") (pin "1") (pinfunction "1_1") (pintype "passive"))
    )
    (net (code "57") (name "Net-(IC2-PA5_(ADC5{slash}PCINT5))") (class "Default")
      (node (ref "IC2") (pin "32") (pinfunction "PA5_(ADC5/PCINT5)_32") (pintype "passive"))
      (node (ref "R12") (pin "1") (pinfunction "1_1") (pintype "passive"))
    )
    (net (code "58") (name "Net-(IC2-PA6_(ADC6{slash}PCINT6))") (class "Default")
      (node (ref "IC2") (pin "31") (pinfunction "PA6_(ADC6/PCINT6)_31") (pintype "passive"))
      (node (ref "R13") (pin "1") (pinfunction "1_1") (pintype "passive"))
    )
    (net (code "59") (name "Net-(IC2-XTAL1)") (class "Default")
      (node (ref "C12") (pin "2") (pinfunction "2_2") (pintype "passive"))
      (node (ref "IC2") (pin "8") (pinfunction "XTAL1_8") (pintype "passive"))
      (node (ref "Y1") (pin "1") (pinfunction "OSC1_1") (pintype "passive"))
    )
    (net (code "60") (name "Net-(IC2-XTAL2)") (class "Default")
      (node (ref "C9") (pin "2") (pinfunction "2_2") (pintype "passive"))
      (node (ref "IC2") (pin "7") (pinfunction "XTAL2_7") (pintype "passive"))
      (node (ref "Y1") (pin "2") (pinfunction "OSC2_2") (pintype "passive"))
    )
    (net (code "61") (name "Net-(U3-K)") (class "Default")
      (node (ref "R5") (pin "2") (pinfunction "2_2") (pintype "passive"))
      (node (ref "U3") (pin "2") (pinfunction "K_2") (pintype "passive"))
    )
    (net (code "62") (name "Net-(U4-K)") (class "Default")
      (node (ref "R15") (pin "1") (pinfunction "1_1") (pintype "passive"))
      (node (ref "U4") (pin "2") (pinfunction "K_2") (pintype "passive"))
    )
    (net (code "63") (name "Net-(U5-K)") (class "Default")
      (node (ref "R17") (pin "1") (pinfunction "1_1") (pintype "passive"))
      (node (ref "U5") (pin "2") (pinfunction "K_2") (pintype "passive"))
    )
    (net (code "64") (name "Net-(U6-COM)") (class "Default")
      (node (ref "C23") (pin "2") (pinfunction "2_2") (pintype "passive"))
      (node (ref "U6") (pin "25") (pinfunction "COM_25") (pintype "passive"))
    )
    (net (code "65") (name "Net-(U6-INA+)") (class "Default")
      (node (ref "C21") (pin "2") (pinfunction "2_2") (pintype "passive"))
      (node (ref "R25") (pin "1") (pinfunction "1_1") (pintype "passive"))
      (node (ref "U6") (pin "2") (pinfunction "INA+_2") (pintype "passive"))
    )
    (net (code "66") (name "Net-(U6-INB+)") (class "Default")
      (node (ref "C26") (pin "2") (pinfunction "2_2") (pintype "passive"))
      (node (ref "R26") (pin "1") (pinfunction "1_1") (pintype "passive"))
      (node (ref "U6") (pin "6") (pinfunction "INB+_6") (pintype "passive"))
    )
    (net (code "67") (name "Net-(U6-REFIN)") (class "Default")
      (node (ref "C22") (pin "2") (pinfunction "2_2") (pintype "passive"))
      (node (ref "U6") (pin "24") (pinfunction "REFIN_24") (pintype "passive"))
    )
    (net (code "68") (name "Net-(U6-REFN)") (class "Default")
      (node (ref "C24") (pin "2") (pinfunction "2_2") (pintype "passive"))
      (node (ref "U6") (pin "26") (pinfunction "REFN_26") (pintype "passive"))
    )
    (net (code "69") (name "Net-(U6-REFP)") (class "Default")
      (node (ref "C25") (pin "2") (pinfunction "2_2") (pintype "passive"))
      (node (ref "U6") (pin "27") (pinfunction "REFP_27") (pintype "passive"))
    )
    (net (code "70") (name "VCC") (class "Default")
      (node (ref "C16") (pin "2") (pinfunction "2_2") (pintype "passive"))
      (node (ref "C17") (pin "2") (pinfunction "2_2") (pintype "passive"))
      (node (ref "C27") (pin "2") (pinfunction "2_2") (pintype "passive"))
      (node (ref "C28") (pin "1") (pinfunction "+_1") (pintype "passive"))
      (node (ref "C29") (pin "2") (pinfunction "2_2") (pintype "passive"))
      (node (ref "C3") (pin "2") (pinfunction "2_2") (pintype "passive"))
      (node (ref "C30") (pin "2") (pinfunction "2_2") (pintype "passive"))
      (node (ref "C31") (pin "1") (pinfunction "+_1") (pintype "passive"))
      (node (ref "C32") (pin "1") (pinfunction "+_1") (pintype "passive"))
      (node (ref "C4") (pin "2") (pinfunction "2_2") (pintype "passive"))
      (node (ref "C41") (pin "1") (pinfunction "+_1") (pintype "passive"))
      (node (ref "C42") (pin "1") (pinfunction "+_1") (pintype "passive"))
      (node (ref "C43") (pin "1") (pinfunction "+_1") (pintype "passive"))
      (node (ref "C44") (pin "1") (pinfunction "+_1") (pintype "passive"))
      (node (ref "C45") (pin "2") (pinfunction "2_2") (pintype "passive"))
      (node (ref "C46") (pin "2") (pinfunction "2_2") (pintype "passive"))
      (node (ref "C47") (pin "2") (pinfunction "2_2") (pintype "passive"))
      (node (ref "C5") (pin "2") (pinfunction "2_2") (pintype "passive"))
      (node (ref "C6") (pin "2") (pinfunction "2_2") (pintype "passive"))
      (node (ref "D1") (pin "1") (pinfunction "A_1") (pintype "passive"))
      (node (ref "D2") (pin "1") (pinfunction "A_1") (pintype "passive"))
      (node (ref "D4") (pin "1") (pinfunction "A_1") (pintype "passive"))
      (node (ref "IC2") (pin "17") (pinfunction "VCC1_17") (pintype "passive"))
      (node (ref "IC2") (pin "38") (pinfunction "VCC_38") (pintype "passive"))
      (node (ref "IC2") (pin "5") (pinfunction "VCC_5") (pintype "passive"))
      (node (ref "J2") (pin "1") (pinfunction "1_1") (pintype "passive"))
      (node (ref "J4") (pin "1") (pinfunction "1_1") (pintype "passive"))
      (node (ref "J44") (pin "1") (pinfunction "1_1") (pintype "passive"))
      (node (ref "J7") (pin "1") (pinfunction "1_1") (pintype "passive"))
      (node (ref "L1") (pin "1") (pinfunction "1_1") (pintype "passive"))
      (node (ref "L2") (pin "1") (pinfunction "1_1") (pintype "passive"))
      (node (ref "L3") (pin "2") (pinfunction "2_2") (pintype "passive"))
      (node (ref "P2") (pin "5") (pinfunction "5_5") (pintype "passive"))
      (node (ref "P6") (pin "1") (pinfunction "1_1") (pintype "passive"))
      (node (ref "P6") (pin "4") (pinfunction "4_4") (pintype "passive"))
      (node (ref "P7") (pin "2") (pinfunction "2_2") (pintype "passive"))
      (node (ref "P8") (pin "2") (pinfunction "2_2") (pintype "passive"))
      (node (ref "R18") (pin "1") (pinfunction "1_1") (pintype "passive"))
      (node (ref "R24") (pin "2") (pinfunction "2_2") (pintype "passive"))
      (node (ref "R3") (pin "2") (pinfunction "2_2") (pintype "passive"))
      (node (ref "U4") (pin "1") (pinfunction "A_1") (pintype "passive"))
      (node (ref "U5") (pin "1") (pinfunction "A_1") (pintype "passive"))
      (node (ref "VCC") (pin "1") (pinfunction "TP_1") (pintype "passive"))
      (node (ref "Y4") (pin "1") (pinfunction "OE/ST_1") (pintype "passive"))
      (node (ref "Y4") (pin "4") (pinfunction "VCC_4") (pintype "passive"))
    )
    (net (code "71") (name "VDAC") (class "Default")
      (node (ref "C13") (pin "2") (pinfunction "2_2") (pintype "passive"))
      (node (ref "IC3") (pin "1") (pinfunction "VDD_1") (pintype "passive"))
      (node (ref "L2") (pin "2") (pinfunction "2_2") (pintype "passive"))
      (node (ref "VR2") (pin "3") (pinfunction "CW_3") (pintype "passive"))
    )
    (net (code "72") (name "VDD_line") (class "Default")
      (node (ref "C8") (pin "2") (pinfunction "2_2") (pintype "passive"))
      (node (ref "D3") (pin "1") (pinfunction "A_1") (pintype "passive"))
      (node (ref "IC1") (pin "8") (pinfunction "VCC_8") (pintype "passive"))
      (node (ref "J1") (pin "4") (pinfunction "4_4") (pintype "passive"))
      (node (ref "P1") (pin "4") (pinfunction "4_4") (pintype "passive"))
      (node (ref "P5") (pin "1") (pinfunction "1_1") (pintype "passive"))
      (node (ref "P5") (pin "3") (pinfunction "3_3") (pintype "passive"))
      (node (ref "R16") (pin "2") (pinfunction "2_2") (pintype "passive"))
      (node (ref "U1") (pin "1") (pinfunction "1_1") (pintype "passive"))
      (node (ref "U3") (pin "1") (pinfunction "A_1") (pintype "passive"))
      (node (ref "U4") (pin "4") (pinfunction "C_4") (pintype "passive"))
    )
    (net (code "73") (name "unconnected-(U1-Pad3)") (class "Default")
      (node (ref "U1") (pin "3") (pinfunction "3_3") (pintype "passive"))
    )
    (net (code "74") (name "unconnected-(Y2-CRYSTAL_1-Pad1)") (class "Default")
      (node (ref "Y2") (pin "1") (pinfunction "CRYSTAL_1_1") (pintype "passive"))
    )
    (net (code "75") (name "unconnected-(Y2-CRYSTAL_2-Pad3)") (class "Default")
      (node (ref "Y2") (pin "3") (pinfunction "CRYSTAL_2_3") (pintype "passive"))
    )
    (net (code "76") (name "unconnected-(Y2-GND_1-Pad2)") (class "Default")
      (node (ref "Y2") (pin "2") (pinfunction "GND_1_2") (pintype "passive"))
    )
    (net (code "77") (name "unconnected-(Y2-GND_2-Pad4)") (class "Default")
      (node (ref "Y2") (pin "4") (pinfunction "GND_2_4") (pintype "passive"))
    )
  )
)
